# Monster_Tile.net
KiCad netlist of a schematic drawn in Altium Designer
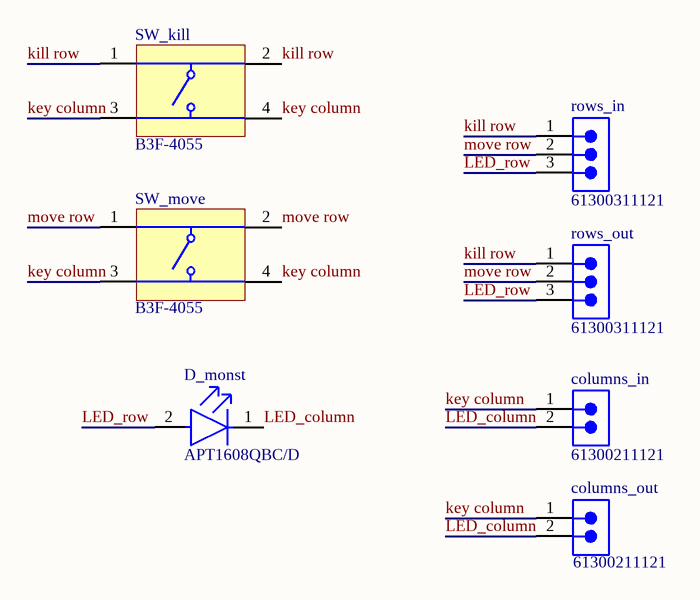
[diagram p0: Monster_Tile.SchDoc]

(export (version "E")
  (design (tool "Eeschema 10.0.6"))
  (components
    (comp (ref "columns_in")
      (value "61300211121")
      (footprint "61300211121")
      (libsource (lib "Altium Content Vault") (part "Header_Male_1R_02P"))
    )
    (comp (ref "columns_out")
      (value "61300211121")
      (footprint "61300211121")
      (libsource (lib "Altium Content Vault") (part "Header_Male_1R_02P"))
    )
    (comp (ref "D_monst")
      (value "APT1608QBC/D")
      (footprint "FP-APT1608QBC-D-MFG")
      (description "LED BLUE CLEAR CHIP SMD")
      (libsource (lib "Altium Content Vault") (part "8706943c75ba83719d021d2fdc84c58"))
    )
    (comp (ref "rows_in")
      (value "61300311121")
      (footprint "61300311121")
      (libsource (lib "Altium Content Vault") (part "Header_Male_1R_03P"))
    )
    (comp (ref "rows_out")
      (value "61300311121")
      (footprint "61300311121")
      (libsource (lib "Altium Content Vault") (part "Header_Male_1R_03P"))
    )
    (comp (ref "SW_kill")
      (value "B3F-4055")
      (footprint "OMRON-B3F-4055_V")
      (description "Tactile Switch, 1 to 50 mA, 100 mOhm Max, 5 to 24 VDC, -25 to 70 degC, 4-Pin THD, RoHS, Bulk")
      (fields (field (name "MANUFACTURER") "OmronElectronics"))
      (libsource (lib "Altium Content Vault") (part "SW-SPST-4_A"))
    )
    (comp (ref "SW_move")
      (value "B3F-4055")
      (footprint "OMRON-B3F-4055_V")
      (description "Tactile Switch, 1 to 50 mA, 100 mOhm Max, 5 to 24 VDC, -25 to 70 degC, 4-Pin THD, RoHS, Bulk")
      (fields (field (name "MANUFACTURER") "OmronElectronics"))
      (libsource (lib "Altium Content Vault") (part "SW-SPST-4_A"))
    )
  )
  (nets
    (net (code "1") (name "/LED_column") (class "Default")
      (node (ref "D_monst") (pin "1") (pinfunction "C_1") (pintype "passive"))
      (node (ref "columns_in") (pin "2") (pinfunction "2_2") (pintype "passive"))
      (node (ref "columns_out") (pin "2") (pinfunction "2_2") (pintype "passive"))
    )
    (net (code "2") (name "/LED_row") (class "Default")
      (node (ref "D_monst") (pin "2") (pinfunction "A_2") (pintype "passive"))
      (node (ref "rows_in") (pin "3") (pinfunction "3_3") (pintype "passive"))
      (node (ref "rows_out") (pin "3") (pinfunction "3_3") (pintype "passive"))
    )
    (net (code "3") (name "/key column") (class "Default")
      (node (ref "SW_kill") (pin "3") (pinfunction "3_3") (pintype "passive"))
      (node (ref "SW_kill") (pin "4") (pinfunction "4_4") (pintype "passive"))
      (node (ref "SW_move") (pin "3") (pinfunction "3_3") (pintype "passive"))
      (node (ref "SW_move") (pin "4") (pinfunction "4_4") (pintype "passive"))
      (node (ref "columns_in") (pin "1") (pinfunction "1_1") (pintype "passive"))
      (node (ref "columns_out") (pin "1") (pinfunction "1_1") (pintype "passive"))
    )
    (net (code "4") (name "/kill row") (class "Default")
      (node (ref "SW_kill") (pin "1") (pinfunction "1_1") (pintype "passive"))
      (node (ref "SW_kill") (pin "2") (pinfunction "2_2") (pintype "passive"))
      (node (ref "rows_in") (pin "1") (pinfunction "1_1") (pintype "passive"))
      (node (ref "rows_out") (pin "1") (pinfunction "1_1") (pintype "passive"))
    )
    (net (code "5") (name "/move row") (class "Default")
      (node (ref "SW_move") (pin "1") (pinfunction "1_1") (pintype "passive"))
      (node (ref "SW_move") (pin "2") (pinfunction "2_2") (pintype "passive"))
      (node (ref "rows_in") (pin "2") (pinfunction "2_2") (pintype "passive"))
      (node (ref "rows_out") (pin "2") (pinfunction "2_2") (pintype "passive"))
    )
  )
)
